# STM32_Schematic_V1.net
KiCad netlist of a schematic drawn in Altium Designer
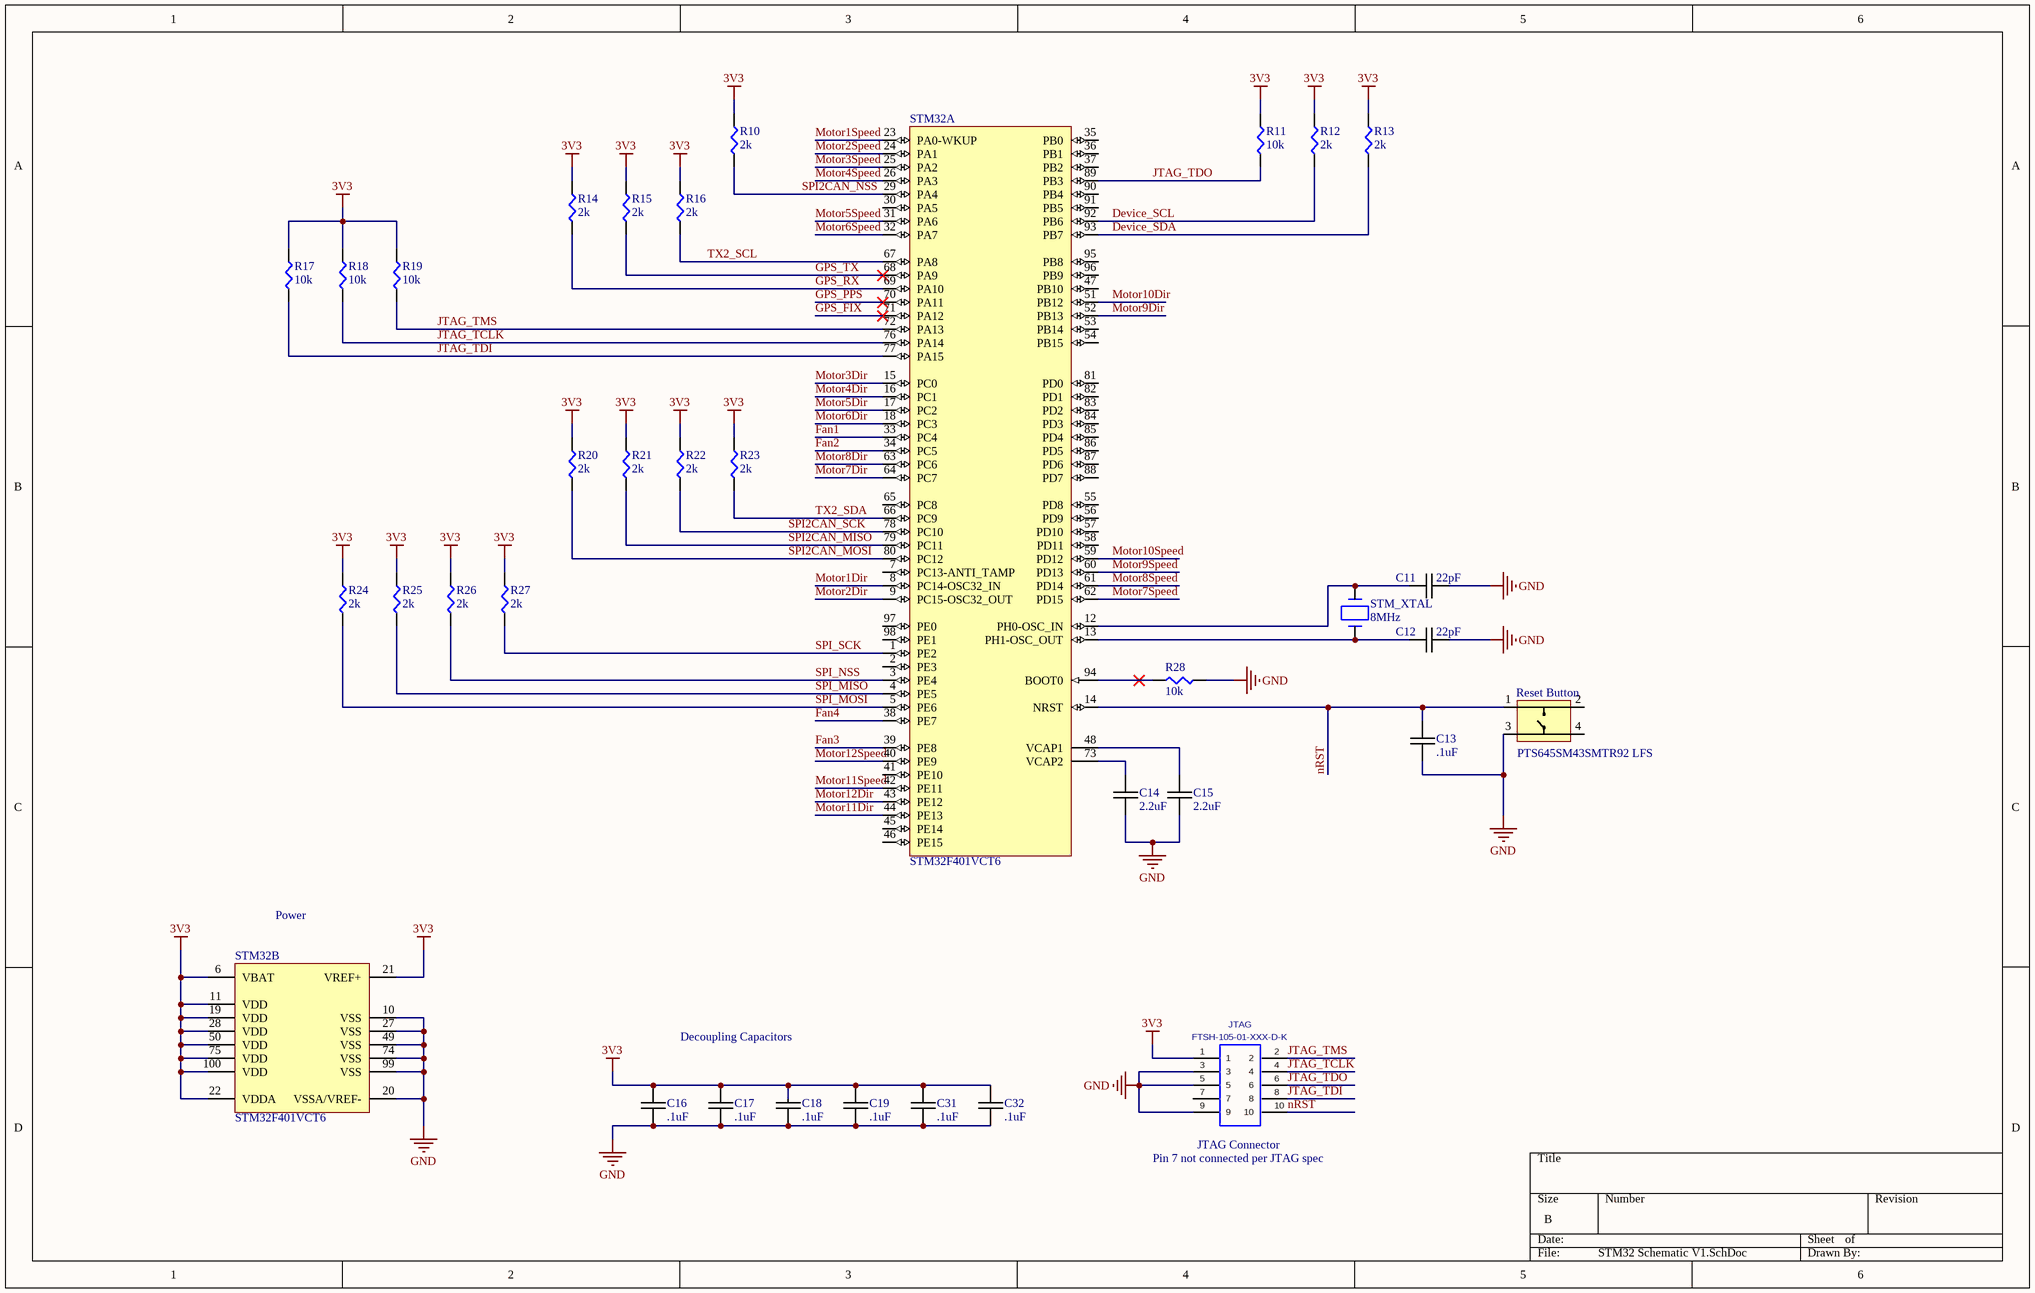
[diagram p0: STM32 Schematic V1.SchDoc]

(export (version "E")
  (design (tool "Eeschema 10.0.6"))
  (components
    (comp (ref "C11")
      (value "22pF")
      (footprint "0805C-GENERIC")
      (description "CAPACITOR 0805 CERAMIC VALUE TO BE DETERMINED")
      (libsource (lib "MARCS Library Main") (part "0805C-TBD"))
    )
    (comp (ref "C12")
      (value "22pF")
      (footprint "0805C-GENERIC")
      (description "CAPACITOR 0805 CERAMIC VALUE TO BE DETERMINED")
      (libsource (lib "MARCS Library Main") (part "0805C-TBD"))
    )
    (comp (ref "C13")
      (value ".1uF")
      (footprint "0805C-GENERIC")
      (description "CAPACITOR 0805 CERAMIC VALUE TO BE DETERMINED")
      (libsource (lib "MARCS Library Main") (part "0805C-TBD"))
    )
    (comp (ref "C14")
      (value "2.2uF")
      (footprint "0805C-GENERIC")
      (description "CAPACITOR 0805 CERAMIC VALUE TO BE DETERMINED")
      (libsource (lib "MARCS Library Main") (part "0805C-TBD"))
    )
    (comp (ref "C15")
      (value "2.2uF")
      (footprint "0805C-GENERIC")
      (description "CAPACITOR 0805 CERAMIC VALUE TO BE DETERMINED")
      (libsource (lib "MARCS Library Main") (part "0805C-TBD"))
    )
    (comp (ref "C16")
      (value ".1uF")
      (footprint "0805C-GENERIC")
      (description "CAPACITOR 0805 CERAMIC VALUE TO BE DETERMINED")
      (libsource (lib "MARCS Library Main") (part "0805C-TBD"))
    )
    (comp (ref "C17")
      (value ".1uF")
      (footprint "0805C-GENERIC")
      (description "CAPACITOR 0805 CERAMIC VALUE TO BE DETERMINED")
      (libsource (lib "MARCS Library Main") (part "0805C-TBD"))
    )
    (comp (ref "C18")
      (value ".1uF")
      (footprint "0805C-GENERIC")
      (description "CAPACITOR 0805 CERAMIC VALUE TO BE DETERMINED")
      (libsource (lib "MARCS Library Main") (part "0805C-TBD"))
    )
    (comp (ref "C19")
      (value ".1uF")
      (footprint "0805C-GENERIC")
      (description "CAPACITOR 0805 CERAMIC VALUE TO BE DETERMINED")
      (libsource (lib "MARCS Library Main") (part "0805C-TBD"))
    )
    (comp (ref "C31")
      (value ".1uF")
      (footprint "0805C-GENERIC")
      (description "CAPACITOR 0805 CERAMIC VALUE TO BE DETERMINED")
      (libsource (lib "MARCS Library Main") (part "0805C-TBD"))
    )
    (comp (ref "C32")
      (value ".1uF")
      (footprint "0805C-GENERIC")
      (description "CAPACITOR 0805 CERAMIC VALUE TO BE DETERMINED")
      (libsource (lib "MARCS Library Main") (part "0805C-TBD"))
    )
    (comp (ref "JTAG")
      (value "FTSH-105-01-XXX-D-K")
      (footprint "FTSH-105-01-XXX-D-K")
      (description "TERMINAL STRIP, .050\"(1.27mm) PITCH, 10 PINS, KEYING OPTION.")
      (fields
        (field (name "MANUFACTURER") "SAMTEC")
        (field (name "CREATED") "September 26, 2016 - Wendy Xin")
      )
      (libsource (lib "MARCS Library Main") (part "FTSH-105-01-XXX-D-K"))
    )
    (comp (ref "R10")
      (value "2k")
      (footprint "0805R-GENERIC")
      (description "RESISTOR 0805 VALUE TO BE DETERMINED")
      (libsource (lib "MARCS Library Main") (part "0805R-TBD"))
    )
    (comp (ref "R11")
      (value "10k")
      (footprint "0805R-GENERIC")
      (description "RESISTOR 0805 VALUE TO BE DETERMINED")
      (libsource (lib "MARCS Library Main") (part "0805R-TBD"))
    )
    (comp (ref "R12")
      (value "2k")
      (footprint "0805R-GENERIC")
      (description "RESISTOR 0805 VALUE TO BE DETERMINED")
      (libsource (lib "MARCS Library Main") (part "0805R-TBD"))
    )
    (comp (ref "R13")
      (value "2k")
      (footprint "0805R-GENERIC")
      (description "RESISTOR 0805 VALUE TO BE DETERMINED")
      (libsource (lib "MARCS Library Main") (part "0805R-TBD"))
    )
    (comp (ref "R14")
      (value "2k")
      (footprint "0805R-GENERIC")
      (description "RESISTOR 0805 VALUE TO BE DETERMINED")
      (libsource (lib "MARCS Library Main") (part "0805R-TBD"))
    )
    (comp (ref "R15")
      (value "2k")
      (footprint "0805R-GENERIC")
      (description "RESISTOR 0805 VALUE TO BE DETERMINED")
      (libsource (lib "MARCS Library Main") (part "0805R-TBD"))
    )
    (comp (ref "R16")
      (value "2k")
      (footprint "0805R-GENERIC")
      (description "RESISTOR 0805 VALUE TO BE DETERMINED")
      (libsource (lib "MARCS Library Main") (part "0805R-TBD"))
    )
    (comp (ref "R17")
      (value "10k")
      (footprint "0805R-GENERIC")
      (description "RESISTOR 0805 VALUE TO BE DETERMINED")
      (libsource (lib "MARCS Library Main") (part "0805R-TBD"))
    )
    (comp (ref "R18")
      (value "10k")
      (footprint "0805R-GENERIC")
      (description "RESISTOR 0805 VALUE TO BE DETERMINED")
      (libsource (lib "MARCS Library Main") (part "0805R-TBD"))
    )
    (comp (ref "R19")
      (value "10k")
      (footprint "0805R-GENERIC")
      (description "RESISTOR 0805 VALUE TO BE DETERMINED")
      (libsource (lib "MARCS Library Main") (part "0805R-TBD"))
    )
    (comp (ref "R20")
      (value "2k")
      (footprint "0805R-GENERIC")
      (description "RESISTOR 0805 VALUE TO BE DETERMINED")
      (libsource (lib "MARCS Library Main") (part "0805R-TBD"))
    )
    (comp (ref "R21")
      (value "2k")
      (footprint "0805R-GENERIC")
      (description "RESISTOR 0805 VALUE TO BE DETERMINED")
      (libsource (lib "MARCS Library Main") (part "0805R-TBD"))
    )
    (comp (ref "R22")
      (value "2k")
      (footprint "0805R-GENERIC")
      (description "RESISTOR 0805 VALUE TO BE DETERMINED")
      (libsource (lib "MARCS Library Main") (part "0805R-TBD"))
    )
    (comp (ref "R23")
      (value "2k")
      (footprint "0805R-GENERIC")
      (description "RESISTOR 0805 VALUE TO BE DETERMINED")
      (libsource (lib "MARCS Library Main") (part "0805R-TBD"))
    )
    (comp (ref "R24")
      (value "2k")
      (footprint "0805R-GENERIC")
      (description "RESISTOR 0805 VALUE TO BE DETERMINED")
      (libsource (lib "MARCS Library Main") (part "0805R-TBD"))
    )
    (comp (ref "R25")
      (value "2k")
      (footprint "0805R-GENERIC")
      (description "RESISTOR 0805 VALUE TO BE DETERMINED")
      (libsource (lib "MARCS Library Main") (part "0805R-TBD"))
    )
    (comp (ref "R26")
      (value "2k")
      (footprint "0805R-GENERIC")
      (description "RESISTOR 0805 VALUE TO BE DETERMINED")
      (libsource (lib "MARCS Library Main") (part "0805R-TBD"))
    )
    (comp (ref "R27")
      (value "2k")
      (footprint "0805R-GENERIC")
      (description "RESISTOR 0805 VALUE TO BE DETERMINED")
      (libsource (lib "MARCS Library Main") (part "0805R-TBD"))
    )
    (comp (ref "R28")
      (value "10k")
      (footprint "0805R-GENERIC")
      (description "RESISTOR 0805 VALUE TO BE DETERMINED")
      (libsource (lib "MARCS Library Main") (part "0805R-TBD"))
    )
    (comp (ref "Reset Button")
      (value "PTS645SM43SMTR92 LFS")
      (footprint "PTS645SM43SMTR92 LFS")
      (libsource (lib "MARCS Library Main") (part "PTS645SM43SMTR92 LFS"))
    )
    (comp (ref "STM32")
      (value "STM32F401VCT6")
      (footprint "STM-LQFP100_V")
      (fields (field (name "MANUFACTURER") "STMicroelectronics"))
      (libsource (lib "MARCS Library Main") (part "STM32F401VCT6"))
    )
    (comp (ref "STM_XTAL")
      (value "8MHz")
      (footprint "GC0800044")
      (description "Diodes Incorporated GC0800044")
      (libsource (lib "MARCS Library Main") (part "GC0800044"))
    )
  )
  (nets
    (net (code "1") (name "/Device_SCL") (class "Default")
      (node (ref "R12") (pin "2") (pintype "passive"))
      (node (ref "STM32") (pin "92") (pinfunction "PB6_92") (pintype "bidirectional"))
    )
    (net (code "2") (name "/Device_SDA") (class "Default")
      (node (ref "R13") (pin "2") (pintype "passive"))
      (node (ref "STM32") (pin "93") (pinfunction "PB7_93") (pintype "bidirectional"))
    )
    (net (code "3") (name "/Fan1") (class "Default")
      (node (ref "STM32") (pin "33") (pinfunction "PC4_33") (pintype "bidirectional"))
    )
    (net (code "4") (name "/Fan2") (class "Default")
      (node (ref "STM32") (pin "34") (pinfunction "PC5_34") (pintype "bidirectional"))
    )
    (net (code "5") (name "/Fan3") (class "Default")
      (node (ref "STM32") (pin "39") (pinfunction "PE8_39") (pintype "bidirectional"))
    )
    (net (code "6") (name "/Fan4") (class "Default")
      (node (ref "STM32") (pin "38") (pinfunction "PE7_38") (pintype "bidirectional"))
    )
    (net (code "7") (name "/GPS_FIX") (class "Default")
      (node (ref "STM32") (pin "71") (pinfunction "PA12_71") (pintype "bidirectional+no_connect"))
    )
    (net (code "8") (name "/GPS_PPS") (class "Default")
      (node (ref "STM32") (pin "70") (pinfunction "PA11_70") (pintype "bidirectional+no_connect"))
    )
    (net (code "9") (name "/GPS_RX") (class "Default")
      (node (ref "R14") (pin "2") (pintype "passive"))
      (node (ref "STM32") (pin "69") (pinfunction "PA10_69") (pintype "bidirectional"))
    )
    (net (code "10") (name "/GPS_TX") (class "Default")
      (node (ref "R15") (pin "2") (pintype "passive"))
      (node (ref "STM32") (pin "68") (pinfunction "PA9_68") (pintype "bidirectional"))
    )
    (net (code "11") (name "/JTAG_TCLK") (class "Default")
      (node (ref "JTAG") (pin "4") (pinfunction "4_4") (pintype "passive"))
      (node (ref "R18") (pin "2") (pintype "passive"))
      (node (ref "STM32") (pin "76") (pinfunction "PA14_76") (pintype "bidirectional"))
    )
    (net (code "12") (name "/JTAG_TDI") (class "Default")
      (node (ref "JTAG") (pin "8") (pinfunction "8_8") (pintype "passive"))
      (node (ref "R17") (pin "2") (pintype "passive"))
      (node (ref "STM32") (pin "77") (pinfunction "PA15_77") (pintype "bidirectional"))
    )
    (net (code "13") (name "/JTAG_TDO") (class "Default")
      (node (ref "JTAG") (pin "6") (pinfunction "6_6") (pintype "passive"))
      (node (ref "R11") (pin "2") (pintype "passive"))
      (node (ref "STM32") (pin "89") (pinfunction "PB3_89") (pintype "bidirectional"))
    )
    (net (code "14") (name "/JTAG_TMS") (class "Default")
      (node (ref "JTAG") (pin "2") (pinfunction "2_2") (pintype "passive"))
      (node (ref "R19") (pin "2") (pintype "passive"))
      (node (ref "STM32") (pin "72") (pinfunction "PA13_72") (pintype "bidirectional"))
    )
    (net (code "15") (name "/Motor1Dir") (class "Default")
      (node (ref "STM32") (pin "8") (pinfunction "PC14-OSC32_IN_8") (pintype "bidirectional"))
    )
    (net (code "16") (name "/Motor1Speed") (class "Default")
      (node (ref "STM32") (pin "23") (pinfunction "PA0-WKUP_23") (pintype "bidirectional"))
    )
    (net (code "17") (name "/Motor2Dir") (class "Default")
      (node (ref "STM32") (pin "9") (pinfunction "PC15-OSC32_OUT_9") (pintype "bidirectional"))
    )
    (net (code "18") (name "/Motor2Speed") (class "Default")
      (node (ref "STM32") (pin "24") (pinfunction "PA1_24") (pintype "bidirectional"))
    )
    (net (code "19") (name "/Motor3Dir") (class "Default")
      (node (ref "STM32") (pin "15") (pinfunction "PC0_15") (pintype "bidirectional"))
    )
    (net (code "20") (name "/Motor3Speed") (class "Default")
      (node (ref "STM32") (pin "25") (pinfunction "PA2_25") (pintype "bidirectional"))
    )
    (net (code "21") (name "/Motor4Dir") (class "Default")
      (node (ref "STM32") (pin "16") (pinfunction "PC1_16") (pintype "bidirectional"))
    )
    (net (code "22") (name "/Motor4Speed") (class "Default")
      (node (ref "STM32") (pin "26") (pinfunction "PA3_26") (pintype "bidirectional"))
    )
    (net (code "23") (name "/Motor5Dir") (class "Default")
      (node (ref "STM32") (pin "17") (pinfunction "PC2_17") (pintype "bidirectional"))
    )
    (net (code "24") (name "/Motor5Speed") (class "Default")
      (node (ref "STM32") (pin "31") (pinfunction "PA6_31") (pintype "bidirectional"))
    )
    (net (code "25") (name "/Motor6Dir") (class "Default")
      (node (ref "STM32") (pin "18") (pinfunction "PC3_18") (pintype "bidirectional"))
    )
    (net (code "26") (name "/Motor6Speed") (class "Default")
      (node (ref "STM32") (pin "32") (pinfunction "PA7_32") (pintype "bidirectional"))
    )
    (net (code "27") (name "/Motor7Dir") (class "Default")
      (node (ref "STM32") (pin "64") (pinfunction "PC7_64") (pintype "bidirectional"))
    )
    (net (code "28") (name "/Motor7Speed") (class "Default")
      (node (ref "STM32") (pin "62") (pinfunction "PD15_62") (pintype "bidirectional"))
    )
    (net (code "29") (name "/Motor8Dir") (class "Default")
      (node (ref "STM32") (pin "63") (pinfunction "PC6_63") (pintype "bidirectional"))
    )
    (net (code "30") (name "/Motor8Speed") (class "Default")
      (node (ref "STM32") (pin "61") (pinfunction "PD14_61") (pintype "bidirectional"))
    )
    (net (code "31") (name "/Motor9Dir") (class "Default")
      (node (ref "STM32") (pin "52") (pinfunction "PB13_52") (pintype "bidirectional"))
    )
    (net (code "32") (name "/Motor9Speed") (class "Default")
      (node (ref "STM32") (pin "60") (pinfunction "PD13_60") (pintype "bidirectional"))
    )
    (net (code "33") (name "/Motor10Dir") (class "Default")
      (node (ref "STM32") (pin "51") (pinfunction "PB12_51") (pintype "bidirectional"))
    )
    (net (code "34") (name "/Motor10Speed") (class "Default")
      (node (ref "STM32") (pin "59") (pinfunction "PD12_59") (pintype "bidirectional"))
    )
    (net (code "35") (name "/Motor11Dir") (class "Default")
      (node (ref "STM32") (pin "44") (pinfunction "PE13_44") (pintype "bidirectional"))
    )
    (net (code "36") (name "/Motor11Speed") (class "Default")
      (node (ref "STM32") (pin "42") (pinfunction "PE11_42") (pintype "bidirectional"))
    )
    (net (code "37") (name "/Motor12Dir") (class "Default")
      (node (ref "STM32") (pin "43") (pinfunction "PE12_43") (pintype "bidirectional"))
    )
    (net (code "38") (name "/Motor12Speed") (class "Default")
      (node (ref "STM32") (pin "40") (pinfunction "PE9_40") (pintype "bidirectional"))
    )
    (net (code "39") (name "/SPI2CAN_MISO") (class "Default")
      (node (ref "R21") (pin "2") (pintype "passive"))
      (node (ref "STM32") (pin "79") (pinfunction "PC11_79") (pintype "bidirectional"))
    )
    (net (code "40") (name "/SPI2CAN_MOSI") (class "Default")
      (node (ref "R20") (pin "2") (pintype "passive"))
      (node (ref "STM32") (pin "80") (pinfunction "PC12_80") (pintype "bidirectional"))
    )
    (net (code "41") (name "/SPI2CAN_NSS") (class "Default")
      (node (ref "R10") (pin "2") (pintype "passive"))
      (node (ref "STM32") (pin "29") (pinfunction "PA4_29") (pintype "bidirectional"))
    )
    (net (code "42") (name "/SPI2CAN_SCK") (class "Default")
      (node (ref "R22") (pin "2") (pintype "passive"))
      (node (ref "STM32") (pin "78") (pinfunction "PC10_78") (pintype "bidirectional"))
    )
    (net (code "43") (name "/SPI_MISO") (class "Default")
      (node (ref "R25") (pin "2") (pintype "passive"))
      (node (ref "STM32") (pin "4") (pinfunction "PE5_4") (pintype "bidirectional"))
    )
    (net (code "44") (name "/SPI_MOSI") (class "Default")
      (node (ref "R24") (pin "2") (pintype "passive"))
      (node (ref "STM32") (pin "5") (pinfunction "PE6_5") (pintype "bidirectional"))
    )
    (net (code "45") (name "/SPI_NSS") (class "Default")
      (node (ref "R26") (pin "2") (pintype "passive"))
      (node (ref "STM32") (pin "3") (pinfunction "PE4_3") (pintype "bidirectional"))
    )
    (net (code "46") (name "/SPI_SCK") (class "Default")
      (node (ref "R27") (pin "2") (pintype "passive"))
      (node (ref "STM32") (pin "1") (pinfunction "PE2_1") (pintype "bidirectional"))
    )
    (net (code "47") (name "/TX2_SCL") (class "Default")
      (node (ref "R16") (pin "2") (pintype "passive"))
      (node (ref "STM32") (pin "67") (pinfunction "PA8_67") (pintype "bidirectional"))
    )
    (net (code "48") (name "/TX2_SDA") (class "Default")
      (node (ref "R23") (pin "2") (pintype "passive"))
      (node (ref "STM32") (pin "66") (pinfunction "PC9_66") (pintype "bidirectional"))
    )
    (net (code "49") (name "/nRST") (class "Default")
      (node (ref "C13") (pin "1") (pintype "passive"))
      (node (ref "JTAG") (pin "10") (pinfunction "10_10") (pintype "passive"))
      (node (ref "Reset Button") (pin "1") (pinfunction "1_1") (pintype "passive"))
      (node (ref "STM32") (pin "14") (pinfunction "NRST_14") (pintype "bidirectional"))
    )
    (net (code "50") (name "3V3") (class "Default")
      (node (ref "C16") (pin "1") (pintype "passive"))
      (node (ref "C17") (pin "1") (pintype "passive"))
      (node (ref "C18") (pin "1") (pintype "passive"))
      (node (ref "C19") (pin "1") (pintype "passive"))
      (node (ref "C31") (pin "1") (pintype "passive"))
      (node (ref "C32") (pin "1") (pintype "passive"))
      (node (ref "JTAG") (pin "1") (pinfunction "1_1") (pintype "passive"))
      (node (ref "R10") (pin "1") (pintype "passive"))
      (node (ref "R11") (pin "1") (pintype "passive"))
      (node (ref "R12") (pin "1") (pintype "passive"))
      (node (ref "R13") (pin "1") (pintype "passive"))
      (node (ref "R14") (pin "1") (pintype "passive"))
      (node (ref "R15") (pin "1") (pintype "passive"))
      (node (ref "R16") (pin "1") (pintype "passive"))
      (node (ref "R17") (pin "1") (pintype "passive"))
      (node (ref "R18") (pin "1") (pintype "passive"))
      (node (ref "R19") (pin "1") (pintype "passive"))
      (node (ref "R20") (pin "1") (pintype "passive"))
      (node (ref "R21") (pin "1") (pintype "passive"))
      (node (ref "R22") (pin "1") (pintype "passive"))
      (node (ref "R23") (pin "1") (pintype "passive"))
      (node (ref "R24") (pin "1") (pintype "passive"))
      (node (ref "R25") (pin "1") (pintype "passive"))
      (node (ref "R26") (pin "1") (pintype "passive"))
      (node (ref "R27") (pin "1") (pintype "passive"))
      (node (ref "STM32") (pin "100") (pinfunction "VDD_100") (pintype "power_in"))
      (node (ref "STM32") (pin "11") (pinfunction "VDD_11") (pintype "power_in"))
      (node (ref "STM32") (pin "19") (pinfunction "VDD_19") (pintype "power_in"))
      (node (ref "STM32") (pin "21") (pinfunction "VREF+_21") (pintype "power_in"))
      (node (ref "STM32") (pin "22") (pinfunction "VDDA_22") (pintype "power_in"))
      (node (ref "STM32") (pin "28") (pinfunction "VDD_28") (pintype "power_in"))
      (node (ref "STM32") (pin "50") (pinfunction "VDD_50") (pintype "power_in"))
      (node (ref "STM32") (pin "6") (pinfunction "VBAT_6") (pintype "power_in"))
      (node (ref "STM32") (pin "75") (pinfunction "VDD_75") (pintype "power_in"))
    )
    (net (code "51") (name "GND") (class "Default")
      (node (ref "C11") (pin "2") (pintype "passive"))
      (node (ref "C12") (pin "2") (pintype "passive"))
      (node (ref "C13") (pin "2") (pintype "passive"))
      (node (ref "C14") (pin "2") (pintype "passive"))
      (node (ref "C15") (pin "2") (pintype "passive"))
      (node (ref "C16") (pin "2") (pintype "passive"))
      (node (ref "C17") (pin "2") (pintype "passive"))
      (node (ref "C18") (pin "2") (pintype "passive"))
      (node (ref "C19") (pin "2") (pintype "passive"))
      (node (ref "C31") (pin "2") (pintype "passive"))
      (node (ref "C32") (pin "2") (pintype "passive"))
      (node (ref "JTAG") (pin "3") (pinfunction "3_3") (pintype "passive"))
      (node (ref "JTAG") (pin "5") (pinfunction "5_5") (pintype "passive"))
      (node (ref "JTAG") (pin "9") (pinfunction "9_9") (pintype "passive"))
      (node (ref "R28") (pin "2") (pintype "passive"))
      (node (ref "Reset Button") (pin "3") (pinfunction "3_3") (pintype "passive"))
      (node (ref "STM32") (pin "10") (pinfunction "VSS_10") (pintype "power_in"))
      (node (ref "STM32") (pin "20") (pinfunction "VSSA/VREF-_20") (pintype "power_in"))
      (node (ref "STM32") (pin "27") (pinfunction "VSS_27") (pintype "power_in"))
      (node (ref "STM32") (pin "49") (pinfunction "VSS_49") (pintype "power_in"))
      (node (ref "STM32") (pin "74") (pinfunction "VSS_74") (pintype "power_in"))
      (node (ref "STM32") (pin "99") (pinfunction "VSS_99") (pintype "power_in"))
    )
    (net (code "52") (name "Net-(STM32A-BOOT0)") (class "Default")
      (node (ref "R28") (pin "1") (pintype "passive"))
      (node (ref "STM32") (pin "94") (pinfunction "BOOT0_94") (pintype "input"))
    )
    (net (code "53") (name "Net-(STM32A-PH0-OSC_IN)") (class "Default")
      (node (ref "C11") (pin "1") (pintype "passive"))
      (node (ref "STM32") (pin "12") (pinfunction "PH0-OSC_IN_12") (pintype "bidirectional"))
      (node (ref "STM_XTAL") (pin "1") (pinfunction "1_1") (pintype "passive"))
    )
    (net (code "54") (name "Net-(STM32A-PH1-OSC_OUT)") (class "Default")
      (node (ref "C12") (pin "1") (pintype "passive"))
      (node (ref "STM32") (pin "13") (pinfunction "PH1-OSC_OUT_13") (pintype "bidirectional"))
      (node (ref "STM_XTAL") (pin "2") (pinfunction "2_2") (pintype "passive"))
    )
    (net (code "55") (name "Net-(STM32A-VCAP1)") (class "Default")
      (node (ref "C15") (pin "1") (pintype "passive"))
      (node (ref "STM32") (pin "48") (pinfunction "VCAP1_48") (pintype "power_in"))
    )
    (net (code "56") (name "Net-(STM32A-VCAP2)") (class "Default")
      (node (ref "C14") (pin "1") (pintype "passive"))
      (node (ref "STM32") (pin "73") (pinfunction "VCAP2_73") (pintype "power_in"))
    )
    (net (code "57") (name "unconnected-(JTAG-Pad7)") (class "Default")
      (node (ref "JTAG") (pin "7") (pinfunction "7_7") (pintype "passive"))
    )
    (net (code "58") (name "unconnected-(Reset Button-Pad2)") (class "Default")
      (node (ref "Reset Button") (pin "2") (pinfunction "2_2") (pintype "passive"))
    )
    (net (code "59") (name "unconnected-(Reset Button-Pad4)") (class "Default")
      (node (ref "Reset Button") (pin "4") (pinfunction "4_4") (pintype "passive"))
    )
    (net (code "60") (name "unconnected-(STM32A-PA5-Pad30)") (class "Default")
      (node (ref "STM32") (pin "30") (pinfunction "PA5_30") (pintype "bidirectional"))
    )
    (net (code "61") (name "unconnected-(STM32A-PB0-Pad35)") (class "Default")
      (node (ref "STM32") (pin "35") (pinfunction "PB0_35") (pintype "bidirectional"))
    )
    (net (code "62") (name "unconnected-(STM32A-PB1-Pad36)") (class "Default")
      (node (ref "STM32") (pin "36") (pinfunction "PB1_36") (pintype "bidirectional"))
    )
    (net (code "63") (name "unconnected-(STM32A-PB2-Pad37)") (class "Default")
      (node (ref "STM32") (pin "37") (pinfunction "PB2_37") (pintype "bidirectional"))
    )
    (net (code "64") (name "unconnected-(STM32A-PB4-Pad90)") (class "Default")
      (node (ref "STM32") (pin "90") (pinfunction "PB4_90") (pintype "bidirectional"))
    )
    (net (code "65") (name "unconnected-(STM32A-PB5-Pad91)") (class "Default")
      (node (ref "STM32") (pin "91") (pinfunction "PB5_91") (pintype "bidirectional"))
    )
    (net (code "66") (name "unconnected-(STM32A-PB8-Pad95)") (class "Default")
      (node (ref "STM32") (pin "95") (pinfunction "PB8_95") (pintype "bidirectional"))
    )
    (net (code "67") (name "unconnected-(STM32A-PB9-Pad96)") (class "Default")
      (node (ref "STM32") (pin "96") (pinfunction "PB9_96") (pintype "bidirectional"))
    )
    (net (code "68") (name "unconnected-(STM32A-PB10-Pad47)") (class "Default")
      (node (ref "STM32") (pin "47") (pinfunction "PB10_47") (pintype "bidirectional"))
    )
    (net (code "69") (name "unconnected-(STM32A-PB14-Pad53)") (class "Default")
      (node (ref "STM32") (pin "53") (pinfunction "PB14_53") (pintype "bidirectional"))
    )
    (net (code "70") (name "unconnected-(STM32A-PB15-Pad54)") (class "Default")
      (node (ref "STM32") (pin "54") (pinfunction "PB15_54") (pintype "bidirectional"))
    )
    (net (code "71") (name "unconnected-(STM32A-PC8-Pad65)") (class "Default")
      (node (ref "STM32") (pin "65") (pinfunction "PC8_65") (pintype "bidirectional"))
    )
    (net (code "72") (name "unconnected-(STM32A-PC13-ANTI_TAMP-Pad7)") (class "Default")
      (node (ref "STM32") (pin "7") (pinfunction "PC13-ANTI_TAMP_7") (pintype "bidirectional"))
    )
    (net (code "73") (name "unconnected-(STM32A-PD0-Pad81)") (class "Default")
      (node (ref "STM32") (pin "81") (pinfunction "PD0_81") (pintype "bidirectional"))
    )
    (net (code "74") (name "unconnected-(STM32A-PD1-Pad82)") (class "Default")
      (node (ref "STM32") (pin "82") (pinfunction "PD1_82") (pintype "bidirectional"))
    )
    (net (code "75") (name "unconnected-(STM32A-PD2-Pad83)") (class "Default")
      (node (ref "STM32") (pin "83") (pinfunction "PD2_83") (pintype "bidirectional"))
    )
    (net (code "76") (name "unconnected-(STM32A-PD3-Pad84)") (class "Default")
      (node (ref "STM32") (pin "84") (pinfunction "PD3_84") (pintype "bidirectional"))
    )
    (net (code "77") (name "unconnected-(STM32A-PD4-Pad85)") (class "Default")
      (node (ref "STM32") (pin "85") (pinfunction "PD4_85") (pintype "bidirectional"))
    )
    (net (code "78") (name "unconnected-(STM32A-PD5-Pad86)") (class "Default")
      (node (ref "STM32") (pin "86") (pinfunction "PD5_86") (pintype "bidirectional"))
    )
    (net (code "79") (name "unconnected-(STM32A-PD6-Pad87)") (class "Default")
      (node (ref "STM32") (pin "87") (pinfunction "PD6_87") (pintype "bidirectional"))
    )
    (net (code "80") (name "unconnected-(STM32A-PD7-Pad88)") (class "Default")
      (node (ref "STM32") (pin "88") (pinfunction "PD7_88") (pintype "bidirectional"))
    )
    (net (code "81") (name "unconnected-(STM32A-PD8-Pad55)") (class "Default")
      (node (ref "STM32") (pin "55") (pinfunction "PD8_55") (pintype "bidirectional"))
    )
    (net (code "82") (name "unconnected-(STM32A-PD9-Pad56)") (class "Default")
      (node (ref "STM32") (pin "56") (pinfunction "PD9_56") (pintype "bidirectional"))
    )
    (net (code "83") (name "unconnected-(STM32A-PD10-Pad57)") (class "Default")
      (node (ref "STM32") (pin "57") (pinfunction "PD10_57") (pintype "bidirectional"))
    )
    (net (code "84") (name "unconnected-(STM32A-PD11-Pad58)") (class "Default")
      (node (ref "STM32") (pin "58") (pinfunction "PD11_58") (pintype "bidirectional"))
    )
    (net (code "85") (name "unconnected-(STM32A-PE0-Pad97)") (class "Default")
      (node (ref "STM32") (pin "97") (pinfunction "PE0_97") (pintype "bidirectional"))
    )
    (net (code "86") (name "unconnected-(STM32A-PE1-Pad98)") (class "Default")
      (node (ref "STM32") (pin "98") (pinfunction "PE1_98") (pintype "bidirectional"))
    )
    (net (code "87") (name "unconnected-(STM32A-PE3-Pad2)") (class "Default")
      (node (ref "STM32") (pin "2") (pinfunction "PE3_2") (pintype "bidirectional"))
    )
    (net (code "88") (name "unconnected-(STM32A-PE10-Pad41)") (class "Default")
      (node (ref "STM32") (pin "41") (pinfunction "PE10_41") (pintype "bidirectional"))
    )
    (net (code "89") (name "unconnected-(STM32A-PE14-Pad45)") (class "Default")
      (node (ref "STM32") (pin "45") (pinfunction "PE14_45") (pintype "bidirectional"))
    )
    (net (code "90") (name "unconnected-(STM32A-PE15-Pad46)") (class "Default")
      (node (ref "STM32") (pin "46") (pinfunction "PE15_46") (pintype "bidirectional"))
    )
  )
)
